# Super_Headphones.net
KiCad netlist of a schematic drawn in EAGLE
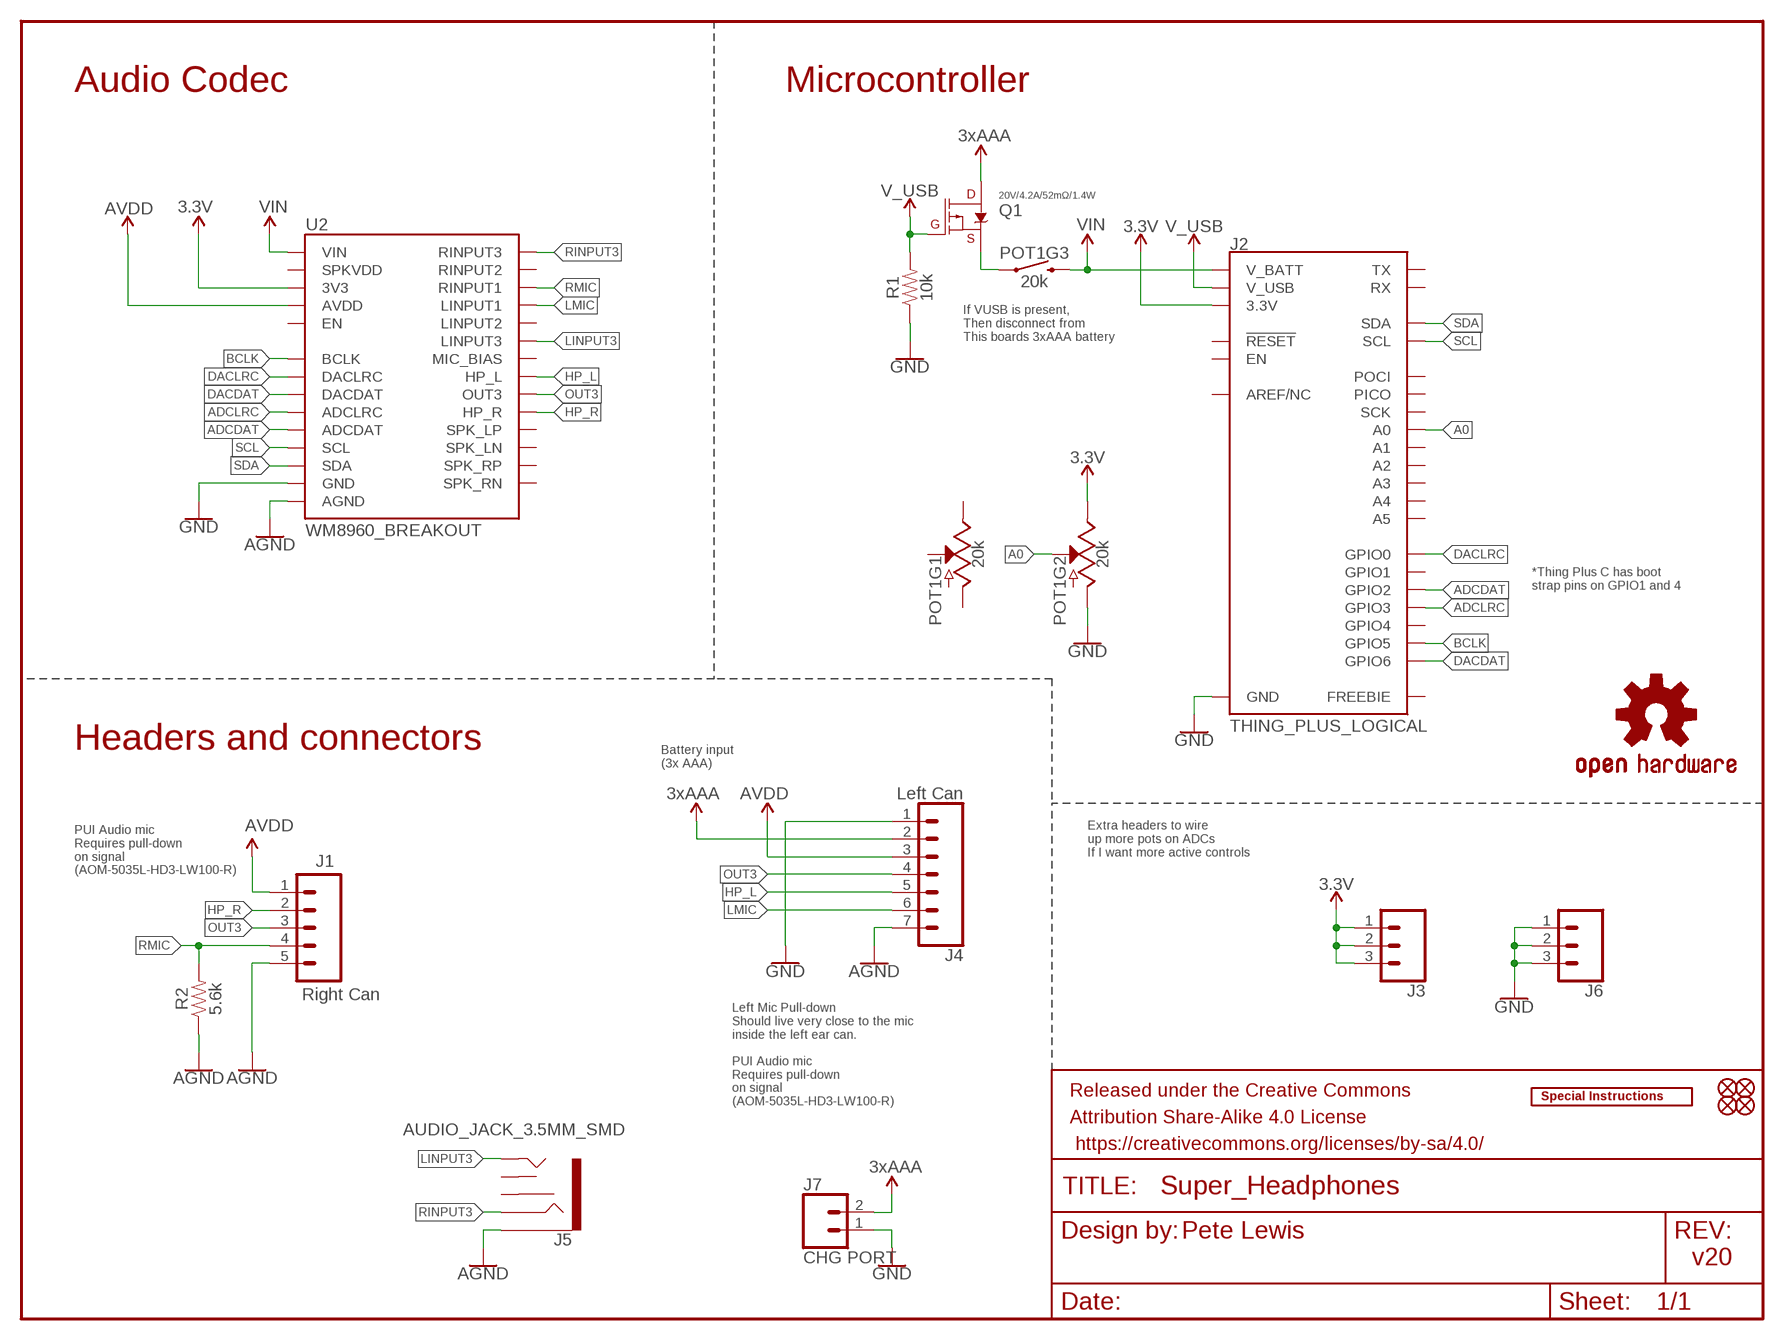
[diagram p0: schematic, sheet 1]

(export (version "E")
  (design (tool "Eeschema 10.0.6"))
  (components
    (comp (ref "FD1")
      (value "FIDUCIALUFIDUCIAL")
      (footprint "eagle-import:FIDUCIAL-MICRO")
      (libsource (lib "eagle-import") (part "FIDUCIALUFIDUCIAL"))
    )
    (comp (ref "FD2")
      (value "FIDUCIALUFIDUCIAL")
      (footprint "eagle-import:FIDUCIAL-MICRO")
      (libsource (lib "eagle-import") (part "FIDUCIALUFIDUCIAL"))
    )
    (comp (ref "FD3")
      (value "FIDUCIALUFIDUCIAL")
      (footprint "eagle-import:FIDUCIAL-MICRO")
      (libsource (lib "eagle-import") (part "FIDUCIALUFIDUCIAL"))
    )
    (comp (ref "FD4")
      (value "FIDUCIALUFIDUCIAL")
      (footprint "eagle-import:FIDUCIAL-MICRO")
      (libsource (lib "eagle-import") (part "FIDUCIALUFIDUCIAL"))
    )
    (comp (ref "FRAME2")
      (value "FRAME-LETTER")
      (footprint "eagle-import:CREATIVE_COMMONS")
      (libsource (lib "eagle-import") (part "FRAME-LETTER"))
    )
    (comp (ref "J1")
      (value "Right Can")
      (footprint "eagle-import:1X05_NO_SILK")
      (libsource (lib "eagle-import") (part "CONN_05NO_SILK"))
    )
    (comp (ref "J2")
      (value "THING_PLUS_LOGICAL")
      (footprint "eagle-import:THING_PLUS")
      (libsource (lib "eagle-import") (part "THING_PLUS_LOGICAL"))
    )
    (comp (ref "J3")
      (value "CONN_031X03_NO_SILK")
      (footprint "eagle-import:1X03_NO_SILK")
      (libsource (lib "eagle-import") (part "CONN_031X03_NO_SILK"))
    )
    (comp (ref "J4")
      (value "Left Can")
      (footprint "eagle-import:1X07_NO_SILK")
      (libsource (lib "eagle-import") (part "CONN_07NO_SILK"))
    )
    (comp (ref "J5")
      (value "AUDIO_JACK_3.5MM_SMD")
      (footprint "eagle-import:AUDIO-JACK-3.5MM-SMD")
      (libsource (lib "eagle-import") (part "AUDIO_JACK_3.5MM_SMD"))
    )
    (comp (ref "J6")
      (value "CONN_031X03_NO_SILK")
      (footprint "eagle-import:1X03_NO_SILK")
      (libsource (lib "eagle-import") (part "CONN_031X03_NO_SILK"))
    )
    (comp (ref "J7")
      (value "CHG PORT")
      (footprint "eagle-import:1X02_NO_SILK")
      (libsource (lib "eagle-import") (part "CONN_021X02_NO_SILK"))
    )
    (comp (ref "LOGO4")
      (value "OSHW-LOGOM")
      (footprint "eagle-import:OSHW-LOGO-M")
      (libsource (lib "eagle-import") (part "OSHW-LOGOM"))
    )
    (comp (ref "LOGO5")
      (value "SPECIAL_INSTRUCTIONS-ORDERING")
      (footprint "eagle-import:ORDERING_INSTRUCTIONS")
      (libsource (lib "eagle-import") (part "SPECIAL_INSTRUCTIONS-ORDERING"))
    )
    (comp (ref "POT1")
      (value "20k")
      (footprint "eagle-import:POT-DUAL-SWITCH-PTH")
      (libsource (lib "eagle-import") (part "POTENTIOMETER_DUAL_W/SWITCH"))
    )
    (comp (ref "Q1")
      (value "20V/4.2A/52mΩ/1.4W")
      (footprint "eagle-import:SOT23-3")
      (libsource (lib "eagle-import") (part "MOSFET_PCH-DMG2305UX-7"))
    )
    (comp (ref "R1")
      (value "10k")
      (footprint "eagle-import:0603")
      (libsource (lib "eagle-import") (part "10KOHM-0603-1/10W-1%"))
    )
    (comp (ref "R2")
      (value "5.6k")
      (footprint "eagle-import:0603")
      (libsource (lib "eagle-import") (part "5.6KOHM-0603-1/10W-1%"))
    )
    (comp (ref "U2")
      (value "WM8960_BREAKOUT")
      (footprint "eagle-import:WM8960_BREAKOUT")
      (libsource (lib "eagle-import") (part "WM8960_BREAKOUT"))
    )
  )
  (nets
    (net (code "1") (name "3.3V") (class "Default")
      (node (ref "J2") (pin "27") (pinfunction "3.3V_27") (pintype "bidirectional"))
      (node (ref "J3") (pin "1") (pinfunction "1_1") (pintype "passive"))
      (node (ref "J3") (pin "2") (pinfunction "2_2") (pintype "passive"))
      (node (ref "J3") (pin "3") (pinfunction "3_3") (pintype "passive"))
      (node (ref "POT1") (pin "B3") (pinfunction "E_B3") (pintype "passive"))
      (node (ref "U2") (pin "3V3") (pinfunction "3V3_3V3") (pintype "bidirectional"))
    )
    (net (code "2") (name "3xAAA") (class "Default")
      (node (ref "J4") (pin "2") (pinfunction "2_2") (pintype "passive"))
      (node (ref "J7") (pin "2") (pinfunction "2_2") (pintype "passive"))
      (node (ref "Q1") (pin "3") (pinfunction "D_3") (pintype "bidirectional"))
    )
    (net (code "3") (name "A0") (class "Default")
      (node (ref "J2") (pin "24") (pinfunction "A0_24") (pintype "bidirectional"))
      (node (ref "POT1") (pin "B2") (pinfunction "S_B2") (pintype "passive"))
    )
    (net (code "4") (name "ADCDAT") (class "Default")
      (node (ref "J2") (pin "7") (pinfunction "GPIO2_7") (pintype "bidirectional"))
      (node (ref "U2") (pin "ADCDAT") (pinfunction "ADCDAT_ADCDAT") (pintype "bidirectional"))
    )
    (net (code "5") (name "ADCLRC") (class "Default")
      (node (ref "J2") (pin "6") (pinfunction "GPIO3_6") (pintype "bidirectional"))
      (node (ref "U2") (pin "ADCLRC") (pinfunction "ADCLRC_ADCLRC") (pintype "bidirectional"))
    )
    (net (code "6") (name "AGND") (class "Default")
      (node (ref "J1") (pin "5") (pinfunction "5_5") (pintype "passive"))
      (node (ref "J4") (pin "7") (pinfunction "7_7") (pintype "passive"))
      (node (ref "J5") (pin "SLEEVE") (pinfunction "SLEEVE_SLEEVE") (pintype "bidirectional"))
      (node (ref "R2") (pin "1") (pinfunction "1_1") (pintype "passive"))
      (node (ref "U2") (pin "GND1") (pinfunction "AGND_GND1") (pintype "bidirectional"))
    )
    (net (code "7") (name "AVDD") (class "Default")
      (node (ref "J1") (pin "1") (pinfunction "1_1") (pintype "passive"))
      (node (ref "J4") (pin "3") (pinfunction "3_3") (pintype "passive"))
      (node (ref "U2") (pin "AVDD") (pinfunction "AVDD_AVDD") (pintype "bidirectional"))
    )
    (net (code "8") (name "BCLK") (class "Default")
      (node (ref "J2") (pin "4") (pinfunction "GPIO5_4") (pintype "bidirectional"))
      (node (ref "U2") (pin "BCLK") (pinfunction "BCLK_BCLK") (pintype "bidirectional"))
    )
    (net (code "9") (name "DACDAT") (class "Default")
      (node (ref "J2") (pin "3") (pinfunction "GPIO6_3") (pintype "bidirectional"))
      (node (ref "U2") (pin "DACDAT") (pinfunction "DACDAT_DACDAT") (pintype "bidirectional"))
    )
    (net (code "10") (name "DACLRC") (class "Default")
      (node (ref "J2") (pin "9") (pinfunction "GPIO0_9") (pintype "bidirectional"))
      (node (ref "U2") (pin "DACLRC") (pinfunction "DACLRC_DACLRC") (pintype "bidirectional"))
    )
    (net (code "11") (name "GND") (class "Default")
      (node (ref "J2") (pin "25") (pinfunction "GND_25") (pintype "bidirectional"))
      (node (ref "J4") (pin "1") (pinfunction "1_1") (pintype "passive"))
      (node (ref "J6") (pin "1") (pinfunction "1_1") (pintype "passive"))
      (node (ref "J6") (pin "2") (pinfunction "2_2") (pintype "passive"))
      (node (ref "J6") (pin "3") (pinfunction "3_3") (pintype "passive"))
      (node (ref "J7") (pin "1") (pinfunction "1_1") (pintype "passive"))
      (node (ref "POT1") (pin "B1") (pinfunction "A_B1") (pintype "passive"))
      (node (ref "R1") (pin "1") (pinfunction "1_1") (pintype "passive"))
      (node (ref "U2") (pin "GND2") (pinfunction "GND_GND2") (pintype "bidirectional"))
      (node (ref "U2") (pin "GND3") (pinfunction "GND_GND3") (pintype "bidirectional"))
      (node (ref "U2") (pin "GND4") (pinfunction "GND_GND4") (pintype "bidirectional"))
      (node (ref "U2") (pin "GND5") (pinfunction "GND_GND5") (pintype "bidirectional"))
      (node (ref "U2") (pin "GND6") (pinfunction "GND_GND6") (pintype "bidirectional"))
    )
    (net (code "12") (name "HP_L") (class "Default")
      (node (ref "J4") (pin "5") (pinfunction "5_5") (pintype "passive"))
      (node (ref "U2") (pin "HP_L") (pinfunction "HP_L_HP_L") (pintype "bidirectional"))
    )
    (net (code "13") (name "HP_R") (class "Default")
      (node (ref "J1") (pin "2") (pinfunction "2_2") (pintype "passive"))
      (node (ref "U2") (pin "HP_R") (pinfunction "HP_R_HP_R") (pintype "bidirectional"))
    )
    (net (code "14") (name "LINPUT3") (class "Default")
      (node (ref "J5") (pin "TIP") (pinfunction "TIP_TIP") (pintype "bidirectional"))
      (node (ref "U2") (pin "LINPUT3") (pinfunction "LINPUT3_LINPUT3") (pintype "bidirectional"))
    )
    (net (code "15") (name "LMIC") (class "Default")
      (node (ref "J4") (pin "6") (pinfunction "6_6") (pintype "passive"))
      (node (ref "U2") (pin "LINPUT1") (pinfunction "LINPUT1_LINPUT1") (pintype "bidirectional"))
    )
    (net (code "16") (name "Net-(POT1C-1)") (class "Default")
      (node (ref "POT1") (pin "SW1") (pinfunction "1_SW1") (pintype "passive"))
      (node (ref "Q1") (pin "2") (pinfunction "S_2") (pintype "bidirectional"))
    )
    (net (code "17") (name "OUT3") (class "Default")
      (node (ref "J1") (pin "3") (pinfunction "3_3") (pintype "passive"))
      (node (ref "J4") (pin "4") (pinfunction "4_4") (pintype "passive"))
      (node (ref "U2") (pin "OUT3") (pinfunction "OUT3_OUT3") (pintype "bidirectional"))
    )
    (net (code "18") (name "RINPUT3") (class "Default")
      (node (ref "J5") (pin "RING") (pinfunction "RING_RING") (pintype "bidirectional"))
      (node (ref "U2") (pin "RINPUT3") (pinfunction "RINPUT3_RINPUT3") (pintype "bidirectional"))
    )
    (net (code "19") (name "RMIC") (class "Default")
      (node (ref "J1") (pin "4") (pinfunction "4_4") (pintype "passive"))
      (node (ref "R2") (pin "2") (pinfunction "2_2") (pintype "passive"))
      (node (ref "U2") (pin "RINPUT1") (pinfunction "RINPUT1_RINPUT1") (pintype "bidirectional"))
    )
    (net (code "20") (name "SCL") (class "Default")
      (node (ref "J2") (pin "2") (pinfunction "SCL_2") (pintype "bidirectional"))
      (node (ref "U2") (pin "SCL") (pinfunction "SCL_SCL") (pintype "bidirectional"))
    )
    (net (code "21") (name "SDA") (class "Default")
      (node (ref "J2") (pin "1") (pinfunction "SDA_1") (pintype "bidirectional"))
      (node (ref "U2") (pin "SDA") (pinfunction "SDA_SDA") (pintype "bidirectional"))
    )
    (net (code "22") (name "VIN") (class "Default")
      (node (ref "J2") (pin "12") (pinfunction "V_BATT_12") (pintype "bidirectional"))
      (node (ref "POT1") (pin "SW2") (pinfunction "2_SW2") (pintype "passive"))
      (node (ref "U2") (pin "VIN") (pinfunction "VIN_VIN") (pintype "bidirectional"))
    )
    (net (code "23") (name "V_USB") (class "Default")
      (node (ref "J2") (pin "10") (pinfunction "V_USB_10") (pintype "bidirectional"))
      (node (ref "Q1") (pin "1") (pinfunction "G_1") (pintype "bidirectional"))
      (node (ref "R1") (pin "2") (pinfunction "2_2") (pintype "passive"))
    )
    (net (code "24") (name "unconnected-(J2-A1-Pad23)") (class "Default")
      (node (ref "J2") (pin "23") (pinfunction "A1_23") (pintype "bidirectional"))
    )
    (net (code "25") (name "unconnected-(J2-A2-Pad22)") (class "Default")
      (node (ref "J2") (pin "22") (pinfunction "A2_22") (pintype "bidirectional"))
    )
    (net (code "26") (name "unconnected-(J2-A3-Pad21)") (class "Default")
      (node (ref "J2") (pin "21") (pinfunction "A3_21") (pintype "bidirectional"))
    )
    (net (code "27") (name "unconnected-(J2-A4-Pad20)") (class "Default")
      (node (ref "J2") (pin "20") (pinfunction "A4_20") (pintype "bidirectional"))
    )
    (net (code "28") (name "unconnected-(J2-A5-Pad19)") (class "Default")
      (node (ref "J2") (pin "19") (pinfunction "A5_19") (pintype "bidirectional"))
    )
    (net (code "29") (name "unconnected-(J2-AREF{slash}NC-Pad26)") (class "Default")
      (node (ref "J2") (pin "26") (pinfunction "AREF/NC_26") (pintype "bidirectional"))
    )
    (net (code "30") (name "unconnected-(J2-EN-Pad11)") (class "Default")
      (node (ref "J2") (pin "11") (pinfunction "EN_11") (pintype "bidirectional"))
    )
    (net (code "31") (name "unconnected-(J2-FREEBIE-Pad13)") (class "Default")
      (node (ref "J2") (pin "13") (pinfunction "FREEBIE_13") (pintype "bidirectional"))
    )
    (net (code "32") (name "unconnected-(J2-GPIO1-Pad8)") (class "Default")
      (node (ref "J2") (pin "8") (pinfunction "GPIO1_8") (pintype "bidirectional"))
    )
    (net (code "33") (name "unconnected-(J2-GPIO4-Pad5)") (class "Default")
      (node (ref "J2") (pin "5") (pinfunction "GPIO4_5") (pintype "bidirectional"))
    )
    (net (code "34") (name "unconnected-(J2-PICO-Pad17)") (class "Default")
      (node (ref "J2") (pin "17") (pinfunction "PICO_17") (pintype "bidirectional"))
    )
    (net (code "35") (name "unconnected-(J2-POCI-Pad16)") (class "Default")
      (node (ref "J2") (pin "16") (pinfunction "POCI_16") (pintype "bidirectional"))
    )
    (net (code "36") (name "unconnected-(J2-RX-Pad15)") (class "Default")
      (node (ref "J2") (pin "15") (pinfunction "RX_15") (pintype "bidirectional"))
    )
    (net (code "37") (name "unconnected-(J2-SCK-Pad18)") (class "Default")
      (node (ref "J2") (pin "18") (pinfunction "SCK_18") (pintype "bidirectional"))
    )
    (net (code "38") (name "unconnected-(J2-TX-Pad14)") (class "Default")
      (node (ref "J2") (pin "14") (pinfunction "TX_14") (pintype "bidirectional"))
    )
    (net (code "39") (name "unconnected-(J2-~{RESET}-Pad28)") (class "Default")
      (node (ref "J2") (pin "28") (pinfunction "~{RESET}_28") (pintype "bidirectional"))
    )
    (net (code "40") (name "unconnected-(J5-PadRSH)") (class "Default")
      (node (ref "J5") (pin "RSH") (pinfunction "RSH_RSH") (pintype "bidirectional"))
    )
    (net (code "41") (name "unconnected-(J5-PadTSH)") (class "Default")
      (node (ref "J5") (pin "TSH") (pinfunction "TSH_TSH") (pintype "bidirectional"))
    )
    (net (code "42") (name "unconnected-(POT1A-A-PadA1)") (class "Default")
      (node (ref "POT1") (pin "A1") (pinfunction "A_A1") (pintype "passive"))
    )
    (net (code "43") (name "unconnected-(POT1A-E-PadA3)") (class "Default")
      (node (ref "POT1") (pin "A3") (pinfunction "E_A3") (pintype "passive"))
    )
    (net (code "44") (name "unconnected-(POT1A-S-PadA2)") (class "Default")
      (node (ref "POT1") (pin "A2") (pinfunction "S_A2") (pintype "passive"))
    )
    (net (code "45") (name "unconnected-(U2-PadEN)") (class "Default")
      (node (ref "U2") (pin "EN") (pinfunction "EN_EN") (pintype "bidirectional"))
    )
    (net (code "46") (name "unconnected-(U2-PadLINPUT2)") (class "Default")
      (node (ref "U2") (pin "LINPUT2") (pinfunction "LINPUT2_LINPUT2") (pintype "bidirectional"))
    )
    (net (code "47") (name "unconnected-(U2-PadMIC_BIAS)") (class "Default")
      (node (ref "U2") (pin "MIC_BIAS") (pinfunction "MIC_BIAS_MIC_BIAS") (pintype "bidirectional"))
    )
    (net (code "48") (name "unconnected-(U2-PadRINPUT2)") (class "Default")
      (node (ref "U2") (pin "RINPUT2") (pinfunction "RINPUT2_RINPUT2") (pintype "bidirectional"))
    )
    (net (code "49") (name "unconnected-(U2-PadSPKVDD)") (class "Default")
      (node (ref "U2") (pin "SPKVDD") (pinfunction "SPKVDD_SPKVDD") (pintype "bidirectional"))
    )
    (net (code "50") (name "unconnected-(U2-PadSPK_LN)") (class "Default")
      (node (ref "U2") (pin "SPK_LN") (pinfunction "SPK_LN_SPK_LN") (pintype "bidirectional"))
    )
    (net (code "51") (name "unconnected-(U2-PadSPK_LP)") (class "Default")
      (node (ref "U2") (pin "SPK_LP") (pinfunction "SPK_LP_SPK_LP") (pintype "bidirectional"))
    )
    (net (code "52") (name "unconnected-(U2-PadSPK_RN)") (class "Default")
      (node (ref "U2") (pin "SPK_RN") (pinfunction "SPK_RN_SPK_RN") (pintype "bidirectional"))
    )
    (net (code "53") (name "unconnected-(U2-PadSPK_RP)") (class "Default")
      (node (ref "U2") (pin "SPK_RP") (pinfunction "SPK_RP_SPK_RP") (pintype "bidirectional"))
    )
  )
)
